# LM13700_v2.net
KiCad netlist of a schematic drawn in EAGLE
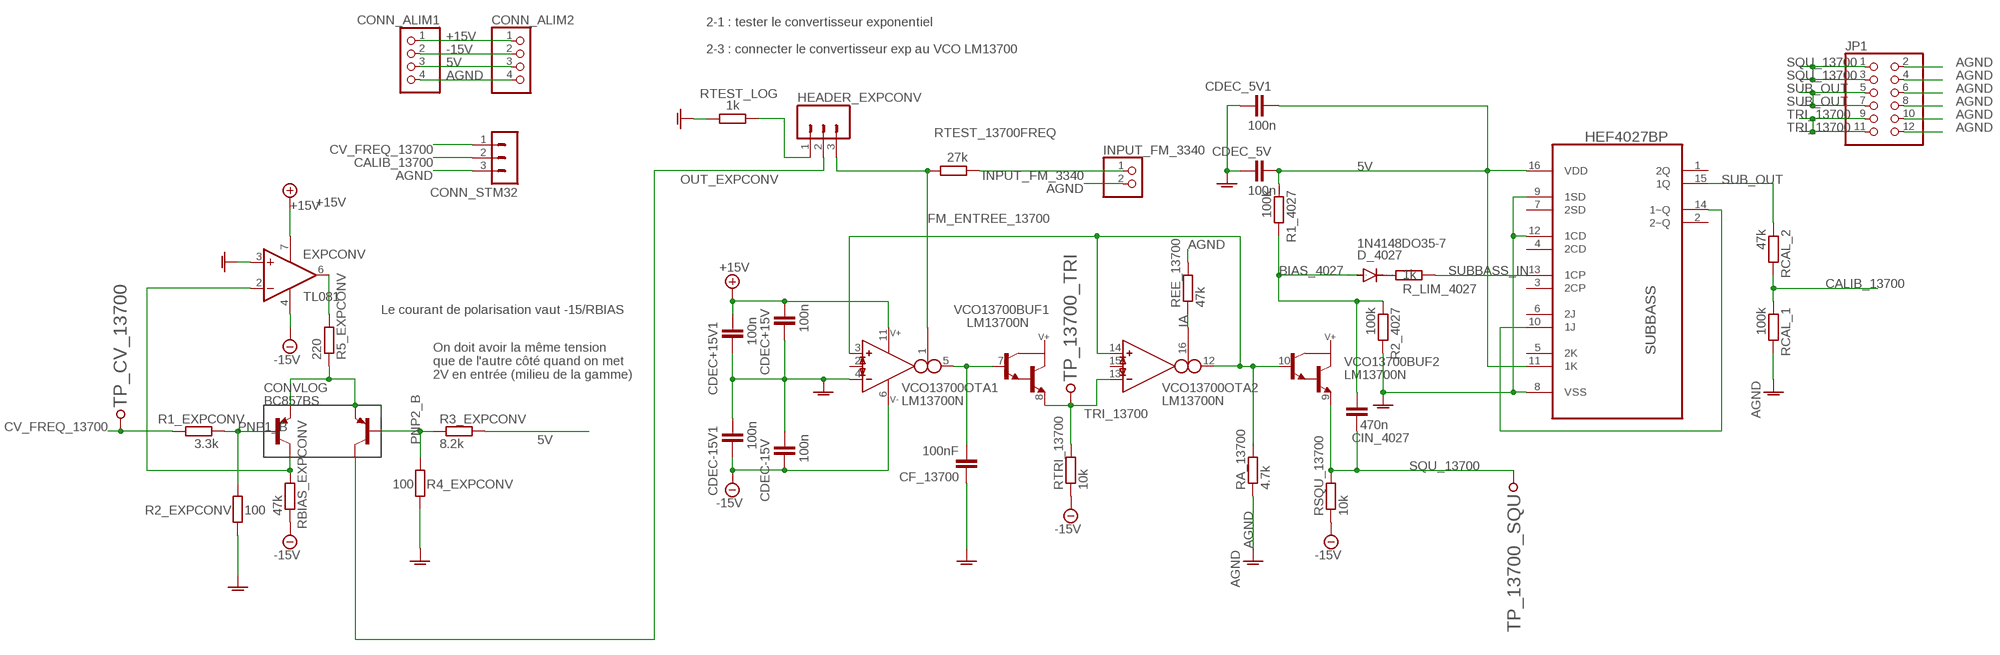
[diagram p0: schematic, sheet 1]

(export (version "E")
  (design (tool "Eeschema 10.0.6"))
  (components
    (comp (ref "CDEC+15V")
      (value "100n")
      (footprint "eagle-import:C075-032X103")
      (libsource (lib "eagle-import") (part "C-EU075-032X103"))
    )
    (comp (ref "CDEC+15V1")
      (value "100n")
      (footprint "eagle-import:C050-025X075")
      (libsource (lib "eagle-import") (part "C-EU050-025X075"))
    )
    (comp (ref "CDEC-15V")
      (value "100n")
      (footprint "eagle-import:C050-025X075")
      (libsource (lib "eagle-import") (part "C-EU050-025X075"))
    )
    (comp (ref "CDEC-15V1")
      (value "100n")
      (footprint "eagle-import:C075-032X103")
      (libsource (lib "eagle-import") (part "C-EU075-032X103"))
    )
    (comp (ref "CDEC_5V")
      (value "100n")
      (footprint "eagle-import:C050-025X075")
      (libsource (lib "eagle-import") (part "C-EU050-025X075"))
    )
    (comp (ref "CDEC_5V1")
      (value "100n")
      (footprint "eagle-import:C050-025X075")
      (libsource (lib "eagle-import") (part "C-EU050-025X075"))
    )
    (comp (ref "CF_13700")
      (value "100nF")
      (footprint "eagle-import:C050-025X075")
      (libsource (lib "eagle-import") (part "C-EU050-025X075"))
    )
    (comp (ref "CIN_4027")
      (value "470n")
      (footprint "eagle-import:C050-025X075")
      (libsource (lib "eagle-import") (part "C-EU050-025X075"))
    )
    (comp (ref "CONN_ALIM1")
      (value "PINHD-1X4")
      (footprint "eagle-import:1X04")
      (libsource (lib "eagle-import") (part "PINHD-1X4"))
    )
    (comp (ref "CONN_ALIM2")
      (value "PINHD-1X4")
      (footprint "eagle-import:1X04")
      (libsource (lib "eagle-import") (part "PINHD-1X4"))
    )
    (comp (ref "CONN_STM32")
      (value "MA03-1")
      (footprint "eagle-import:MA03-1")
      (libsource (lib "eagle-import") (part "MA03-1"))
    )
    (comp (ref "CONVLOG")
      (value "BC857BS")
      (footprint "eagle-import:DIL06")
      (libsource (lib "eagle-import") (part "BC857BS"))
    )
    (comp (ref "D_4027")
      (value "1N4148DO35-7")
      (footprint "eagle-import:DO35-7")
      (libsource (lib "eagle-import") (part "1N4148DO35-7"))
    )
    (comp (ref "EXPCONV")
      (value "TL081")
      (footprint "eagle-import:DIL08")
      (libsource (lib "eagle-import") (part "1AMP_P7+4N"))
    )
    (comp (ref "HEADER_EXPCONV")
      (value "M03")
      (footprint "eagle-import:03P")
      (libsource (lib "eagle-import") (part "M03"))
    )
    (comp (ref "INPUT_FM_3340")
      (value "PINHD-1X2")
      (footprint "eagle-import:1X02")
      (libsource (lib "eagle-import") (part "PINHD-1X2"))
    )
    (comp (ref "JP1")
      (value "PINHD-2X6")
      (footprint "eagle-import:2X06")
      (libsource (lib "eagle-import") (part "PINHD-2X6"))
    )
    (comp (ref "R1_4027")
      (value "100k")
      (footprint "eagle-import:0204_7")
      (libsource (lib "eagle-import") (part "R-EU_0204/7"))
    )
    (comp (ref "R1_EXPCONV")
      (value "3.3k")
      (footprint "eagle-import:0204_7")
      (libsource (lib "eagle-import") (part "R-EU_0204/7"))
    )
    (comp (ref "R2_4027")
      (value "100k")
      (footprint "eagle-import:0204_7")
      (libsource (lib "eagle-import") (part "R-EU_0204/7"))
    )
    (comp (ref "R2_EXPCONV")
      (value "100")
      (footprint "eagle-import:0204_7")
      (libsource (lib "eagle-import") (part "R-EU_0204/7"))
    )
    (comp (ref "R3_EXPCONV")
      (value "8.2k")
      (footprint "eagle-import:0204_7")
      (libsource (lib "eagle-import") (part "R-EU_0204/7"))
    )
    (comp (ref "R4_EXPCONV")
      (value "100")
      (footprint "eagle-import:0204_7")
      (libsource (lib "eagle-import") (part "R-EU_0204/7"))
    )
    (comp (ref "R5_EXPCONV")
      (value "220")
      (footprint "eagle-import:0204_7")
      (libsource (lib "eagle-import") (part "R-EU_0204/7"))
    )
    (comp (ref "RA_13700")
      (value "4.7k")
      (footprint "eagle-import:0204_7")
      (libsource (lib "eagle-import") (part "R-EU_0204/7"))
    )
    (comp (ref "RBIAS_EXPCONV")
      (value "47k")
      (footprint "eagle-import:0204_7")
      (libsource (lib "eagle-import") (part "R-EU_0204/7"))
    )
    (comp (ref "RCAL_1")
      (value "100k")
      (footprint "eagle-import:0204_7")
      (libsource (lib "eagle-import") (part "R-EU_0204/7"))
    )
    (comp (ref "RCAL_2")
      (value "47k")
      (footprint "eagle-import:0204_7")
      (libsource (lib "eagle-import") (part "R-EU_0204/7"))
    )
    (comp (ref "REE_13700")
      (value "47k")
      (footprint "eagle-import:0204_7")
      (libsource (lib "eagle-import") (part "R-EU_0204/7"))
    )
    (comp (ref "RSQU_13700")
      (value "10k")
      (footprint "eagle-import:0204_7")
      (libsource (lib "eagle-import") (part "R-EU_0204/7"))
    )
    (comp (ref "RTEST_13700FREQ")
      (value "27k")
      (footprint "eagle-import:0204_7")
      (libsource (lib "eagle-import") (part "R-EU_0204/7"))
    )
    (comp (ref "RTEST_LOG")
      (value "1k")
      (footprint "eagle-import:0204_7")
      (libsource (lib "eagle-import") (part "R-EU_0204/7"))
    )
    (comp (ref "RTRI_13700")
      (value "10k")
      (footprint "eagle-import:0204_7")
      (libsource (lib "eagle-import") (part "R-EU_0204/7"))
    )
    (comp (ref "R_LIM_4027")
      (value "1k")
      (footprint "eagle-import:0204_7")
      (libsource (lib "eagle-import") (part "R-EU_0204/7"))
    )
    (comp (ref "SUBBASS")
      (value "HEF4027BP")
      (footprint "eagle-import:DIP254P762X420-16")
      (fields (field (name "MF") "NXP Semiconductors"))
      (libsource (lib "eagle-import") (part "HEF4027BP"))
    )
    (comp (ref "TP_13700_SQU")
      (value "TESTPOINT")
      (footprint "eagle-import:TESTPOINT_63")
      (libsource (lib "eagle-import") (part "TESTPOINT"))
    )
    (comp (ref "TP_13700_TRI")
      (value "TESTPOINT")
      (footprint "eagle-import:TESTPOINT_63")
      (libsource (lib "eagle-import") (part "TESTPOINT"))
    )
    (comp (ref "TP_CV_13700")
      (value "TESTPOINT")
      (footprint "eagle-import:TESTPOINT_63")
      (libsource (lib "eagle-import") (part "TESTPOINT"))
    )
    (comp (ref "VCO13700")
      (value "LM13700N")
      (footprint "eagle-import:DIL16")
      (libsource (lib "eagle-import") (part "LM13700N"))
    )
  )
  (nets
    (net (code "1") (name "+15V") (class "Default")
      (node (ref "CDEC+15V") (pin "1") (pinfunction "1_1") (pintype "passive"))
      (node (ref "CDEC+15V1") (pin "1") (pinfunction "1_1") (pintype "passive"))
      (node (ref "CONN_ALIM1") (pin "1") (pinfunction "1_1") (pintype "passive"))
      (node (ref "CONN_ALIM2") (pin "1") (pinfunction "1_1") (pintype "passive"))
      (node (ref "EXPCONV") (pin "7") (pinfunction "V+_7") (pintype "power_in"))
      (node (ref "VCO13700") (pin "11") (pinfunction "V+_11") (pintype "power_in"))
    )
    (net (code "2") (name "-15V") (class "Default")
      (node (ref "CDEC-15V") (pin "2") (pinfunction "2_2") (pintype "passive"))
      (node (ref "CDEC-15V1") (pin "2") (pinfunction "2_2") (pintype "passive"))
      (node (ref "CONN_ALIM1") (pin "2") (pinfunction "2_2") (pintype "passive"))
      (node (ref "CONN_ALIM2") (pin "2") (pinfunction "2_2") (pintype "passive"))
      (node (ref "EXPCONV") (pin "4") (pinfunction "V-_4") (pintype "power_in"))
      (node (ref "RBIAS_EXPCONV") (pin "1") (pinfunction "1_1") (pintype "passive"))
      (node (ref "RSQU_13700") (pin "1") (pinfunction "1_1") (pintype "passive"))
      (node (ref "RTRI_13700") (pin "1") (pinfunction "1_1") (pintype "passive"))
      (node (ref "VCO13700") (pin "6") (pinfunction "V-_6") (pintype "power_in"))
    )
    (net (code "3") (name "/5V") (class "Default")
      (node (ref "CDEC_5V") (pin "1") (pinfunction "1_1") (pintype "passive"))
      (node (ref "CDEC_5V1") (pin "1") (pinfunction "1_1") (pintype "passive"))
      (node (ref "CONN_ALIM1") (pin "3") (pinfunction "3_3") (pintype "passive"))
      (node (ref "CONN_ALIM2") (pin "3") (pinfunction "3_3") (pintype "passive"))
      (node (ref "R1_4027") (pin "1") (pinfunction "1_1") (pintype "passive"))
      (node (ref "R3_EXPCONV") (pin "2") (pinfunction "2_2") (pintype "passive"))
      (node (ref "SUBBASS") (pin "11") (pinfunction "1K_11") (pintype "input"))
      (node (ref "SUBBASS") (pin "16") (pinfunction "VDD_16") (pintype "power_in"))
    )
    (net (code "4") (name "/BIAS_4027") (class "Default")
      (node (ref "CIN_4027") (pin "1") (pinfunction "1_1") (pintype "passive"))
      (node (ref "D_4027") (pin "A") (pinfunction "A_A") (pintype "passive"))
      (node (ref "R1_4027") (pin "2") (pinfunction "2_2") (pintype "passive"))
      (node (ref "R2_4027") (pin "1") (pinfunction "1_1") (pintype "passive"))
    )
    (net (code "5") (name "/CALIB_13700") (class "Default")
      (node (ref "CONN_STM32") (pin "2") (pinfunction "2_2") (pintype "passive"))
      (node (ref "RCAL_1") (pin "1") (pinfunction "1_1") (pintype "passive"))
      (node (ref "RCAL_2") (pin "2") (pinfunction "2_2") (pintype "passive"))
    )
    (net (code "6") (name "/CV_FREQ_13700") (class "Default")
      (node (ref "CONN_STM32") (pin "1") (pinfunction "1_1") (pintype "passive"))
      (node (ref "R1_EXPCONV") (pin "2") (pinfunction "2_2") (pintype "passive"))
      (node (ref "TP_CV_13700") (pin "P$1") (pinfunction "P$1_P$1") (pintype "passive"))
    )
    (net (code "7") (name "/FM_ENTREE_13700") (class "Default")
      (node (ref "HEADER_EXPCONV") (pin "3") (pinfunction "3_3") (pintype "passive"))
      (node (ref "RTEST_13700FREQ") (pin "2") (pinfunction "2_2") (pintype "passive"))
      (node (ref "VCO13700") (pin "1") (pinfunction "I_BIAS_1") (pintype "input"))
    )
    (net (code "8") (name "/IA") (class "Default")
      (node (ref "REE_13700") (pin "1") (pinfunction "1_1") (pintype "passive"))
      (node (ref "VCO13700") (pin "16") (pinfunction "I_BIAS_16") (pintype "input"))
    )
    (net (code "9") (name "/INPUT_FM_3340") (class "Default")
      (node (ref "INPUT_FM_3340") (pin "1") (pinfunction "1_1") (pintype "passive"))
      (node (ref "RTEST_13700FREQ") (pin "1") (pinfunction "1_1") (pintype "passive"))
    )
    (net (code "10") (name "/OUT_EXPCONV") (class "Default")
      (node (ref "CONVLOG") (pin "3") (pinfunction "C2_3") (pintype "passive"))
      (node (ref "HEADER_EXPCONV") (pin "2") (pinfunction "2_2") (pintype "passive"))
    )
    (net (code "11") (name "/PNP1_B") (class "Default")
      (node (ref "CONVLOG") (pin "2") (pinfunction "B1_2") (pintype "passive"))
      (node (ref "R1_EXPCONV") (pin "1") (pinfunction "1_1") (pintype "passive"))
      (node (ref "R2_EXPCONV") (pin "1") (pinfunction "1_1") (pintype "passive"))
    )
    (net (code "12") (name "/PNP2_B") (class "Default")
      (node (ref "CONVLOG") (pin "5") (pinfunction "B2_5") (pintype "passive"))
      (node (ref "R3_EXPCONV") (pin "1") (pinfunction "1_1") (pintype "passive"))
      (node (ref "R4_EXPCONV") (pin "1") (pinfunction "1_1") (pintype "passive"))
    )
    (net (code "13") (name "/SQU_13700") (class "Default")
      (node (ref "CIN_4027") (pin "2") (pinfunction "2_2") (pintype "passive"))
      (node (ref "JP1") (pin "1") (pinfunction "1_1") (pintype "passive"))
      (node (ref "JP1") (pin "3") (pinfunction "3_3") (pintype "passive"))
      (node (ref "RSQU_13700") (pin "2") (pinfunction "2_2") (pintype "passive"))
      (node (ref "TP_13700_SQU") (pin "P$1") (pinfunction "P$1_P$1") (pintype "passive"))
      (node (ref "VCO13700") (pin "9") (pinfunction "E_9") (pintype "passive"))
    )
    (net (code "14") (name "/SUBBASS_IN") (class "Default")
      (node (ref "R_LIM_4027") (pin "1") (pinfunction "1_1") (pintype "passive"))
      (node (ref "SUBBASS") (pin "13") (pinfunction "1CP_13") (pintype "input"))
    )
    (net (code "15") (name "/SUB_OUT") (class "Default")
      (node (ref "JP1") (pin "5") (pinfunction "5_5") (pintype "passive"))
      (node (ref "JP1") (pin "7") (pinfunction "7_7") (pintype "passive"))
      (node (ref "RCAL_2") (pin "1") (pinfunction "1_1") (pintype "passive"))
      (node (ref "SUBBASS") (pin "15") (pinfunction "1Q_15") (pintype "output"))
    )
    (net (code "16") (name "/TRI_13700") (class "Default")
      (node (ref "JP1") (pin "11") (pinfunction "11_11") (pintype "passive"))
      (node (ref "JP1") (pin "9") (pinfunction "9_9") (pintype "passive"))
      (node (ref "RTRI_13700") (pin "2") (pinfunction "2_2") (pintype "passive"))
      (node (ref "TP_13700_TRI") (pin "P$1") (pinfunction "P$1_P$1") (pintype "passive"))
      (node (ref "VCO13700") (pin "13") (pinfunction "IN_N_13") (pintype "input"))
      (node (ref "VCO13700") (pin "8") (pinfunction "E_8") (pintype "passive"))
    )
    (net (code "17") (name "AGND") (class "Default")
      (node (ref "CDEC+15V") (pin "2") (pinfunction "2_2") (pintype "passive"))
      (node (ref "CDEC+15V1") (pin "2") (pinfunction "2_2") (pintype "passive"))
      (node (ref "CDEC-15V") (pin "1") (pinfunction "1_1") (pintype "passive"))
      (node (ref "CDEC-15V1") (pin "1") (pinfunction "1_1") (pintype "passive"))
      (node (ref "CDEC_5V") (pin "2") (pinfunction "2_2") (pintype "passive"))
      (node (ref "CDEC_5V1") (pin "2") (pinfunction "2_2") (pintype "passive"))
      (node (ref "CF_13700") (pin "1") (pinfunction "1_1") (pintype "passive"))
      (node (ref "CONN_ALIM1") (pin "4") (pinfunction "4_4") (pintype "passive"))
      (node (ref "CONN_ALIM2") (pin "4") (pinfunction "4_4") (pintype "passive"))
      (node (ref "CONN_STM32") (pin "3") (pinfunction "3_3") (pintype "passive"))
      (node (ref "EXPCONV") (pin "3") (pinfunction "+IN_3") (pintype "input"))
      (node (ref "INPUT_FM_3340") (pin "2") (pinfunction "2_2") (pintype "passive"))
      (node (ref "JP1") (pin "10") (pinfunction "10_10") (pintype "passive"))
      (node (ref "JP1") (pin "12") (pinfunction "12_12") (pintype "passive"))
      (node (ref "JP1") (pin "2") (pinfunction "2_2") (pintype "passive"))
      (node (ref "JP1") (pin "4") (pinfunction "4_4") (pintype "passive"))
      (node (ref "JP1") (pin "6") (pinfunction "6_6") (pintype "passive"))
      (node (ref "JP1") (pin "8") (pinfunction "8_8") (pintype "passive"))
      (node (ref "R2_4027") (pin "2") (pinfunction "2_2") (pintype "passive"))
      (node (ref "R2_EXPCONV") (pin "2") (pinfunction "2_2") (pintype "passive"))
      (node (ref "R4_EXPCONV") (pin "2") (pinfunction "2_2") (pintype "passive"))
      (node (ref "RA_13700") (pin "1") (pinfunction "1_1") (pintype "passive"))
      (node (ref "RCAL_1") (pin "2") (pinfunction "2_2") (pintype "passive"))
      (node (ref "REE_13700") (pin "2") (pinfunction "2_2") (pintype "passive"))
      (node (ref "RTEST_LOG") (pin "2") (pinfunction "2_2") (pintype "passive"))
      (node (ref "SUBBASS") (pin "12") (pinfunction "1CD_12") (pintype "input"))
      (node (ref "SUBBASS") (pin "8") (pinfunction "VSS_8") (pintype "passive"))
      (node (ref "SUBBASS") (pin "9") (pinfunction "1SD_9") (pintype "input"))
      (node (ref "VCO13700") (pin "4") (pinfunction "IN_N_4") (pintype "input"))
    )
    (net (code "18") (name "Net-(CONVLOG-C1)") (class "Default")
      (node (ref "CONVLOG") (pin "6") (pinfunction "C1_6") (pintype "passive"))
      (node (ref "EXPCONV") (pin "2") (pinfunction "-IN_2") (pintype "input"))
      (node (ref "RBIAS_EXPCONV") (pin "2") (pinfunction "2_2") (pintype "passive"))
    )
    (net (code "19") (name "Net-(CONVLOG-E1)") (class "Default")
      (node (ref "CONVLOG") (pin "1") (pinfunction "E1_1") (pintype "passive"))
      (node (ref "CONVLOG") (pin "4") (pinfunction "E2_4") (pintype "passive"))
      (node (ref "R5_EXPCONV") (pin "1") (pinfunction "1_1") (pintype "passive"))
    )
    (net (code "20") (name "Net-(D_4027-PadC)") (class "Default")
      (node (ref "D_4027") (pin "C") (pinfunction "C_C") (pintype "passive"))
      (node (ref "R_LIM_4027") (pin "2") (pinfunction "2_2") (pintype "passive"))
    )
    (net (code "21") (name "Net-(EXPCONV-OUT)") (class "Default")
      (node (ref "EXPCONV") (pin "6") (pinfunction "OUT_6") (pintype "output"))
      (node (ref "R5_EXPCONV") (pin "2") (pinfunction "2_2") (pintype "passive"))
    )
    (net (code "22") (name "Net-(HEADER_EXPCONV-Pad1)") (class "Default")
      (node (ref "HEADER_EXPCONV") (pin "1") (pinfunction "1_1") (pintype "passive"))
      (node (ref "RTEST_LOG") (pin "1") (pinfunction "1_1") (pintype "passive"))
    )
    (net (code "23") (name "Net-(SUBBASS-1J)") (class "Default")
      (node (ref "SUBBASS") (pin "10") (pinfunction "1J_10") (pintype "input"))
      (node (ref "SUBBASS") (pin "14") (pinfunction "1~{Q}_14") (pintype "output"))
    )
    (net (code "24") (name "Net-(VCO13700A-B)") (class "Default")
      (node (ref "CF_13700") (pin "2") (pinfunction "2_2") (pintype "passive"))
      (node (ref "VCO13700") (pin "5") (pinfunction "OUT_5") (pintype "output"))
      (node (ref "VCO13700") (pin "7") (pinfunction "B_7") (pintype "passive"))
    )
    (net (code "25") (name "Net-(VCO13700B-B)") (class "Default")
      (node (ref "RA_13700") (pin "2") (pinfunction "2_2") (pintype "passive"))
      (node (ref "VCO13700") (pin "10") (pinfunction "B_10") (pintype "passive"))
      (node (ref "VCO13700") (pin "12") (pinfunction "OUT_12") (pintype "output"))
      (node (ref "VCO13700") (pin "14") (pinfunction "IN_P_14") (pintype "input"))
      (node (ref "VCO13700") (pin "3") (pinfunction "IN_P_3") (pintype "input"))
    )
    (net (code "26") (name "unconnected-(SUBBASS-2CD-Pad4)") (class "Default")
      (node (ref "SUBBASS") (pin "4") (pinfunction "2CD_4") (pintype "input"))
    )
    (net (code "27") (name "unconnected-(SUBBASS-2CP-Pad3)") (class "Default")
      (node (ref "SUBBASS") (pin "3") (pinfunction "2CP_3") (pintype "input"))
    )
    (net (code "28") (name "unconnected-(SUBBASS-2J-Pad6)") (class "Default")
      (node (ref "SUBBASS") (pin "6") (pinfunction "2J_6") (pintype "input"))
    )
    (net (code "29") (name "unconnected-(SUBBASS-2K-Pad5)") (class "Default")
      (node (ref "SUBBASS") (pin "5") (pinfunction "2K_5") (pintype "input"))
    )
    (net (code "30") (name "unconnected-(SUBBASS-2Q-Pad1)") (class "Default")
      (node (ref "SUBBASS") (pin "1") (pinfunction "2Q_1") (pintype "output"))
    )
    (net (code "31") (name "unconnected-(SUBBASS-2SD-Pad7)") (class "Default")
      (node (ref "SUBBASS") (pin "7") (pinfunction "2SD_7") (pintype "input"))
    )
    (net (code "32") (name "unconnected-(SUBBASS-2~{Q}-Pad2)") (class "Default")
      (node (ref "SUBBASS") (pin "2") (pinfunction "2~{Q}_2") (pintype "output"))
    )
    (net (code "33") (name "unconnected-(VCO13700C-I_DIODE-Pad2)") (class "Default")
      (node (ref "VCO13700") (pin "2") (pinfunction "I_DIODE_2") (pintype "input"))
    )
    (net (code "34") (name "unconnected-(VCO13700D-I_DIODE-Pad15)") (class "Default")
      (node (ref "VCO13700") (pin "15") (pinfunction "I_DIODE_15") (pintype "input"))
    )
  )
)
